# Input_Stage.net
KiCad netlist of a schematic drawn in Altium Designer
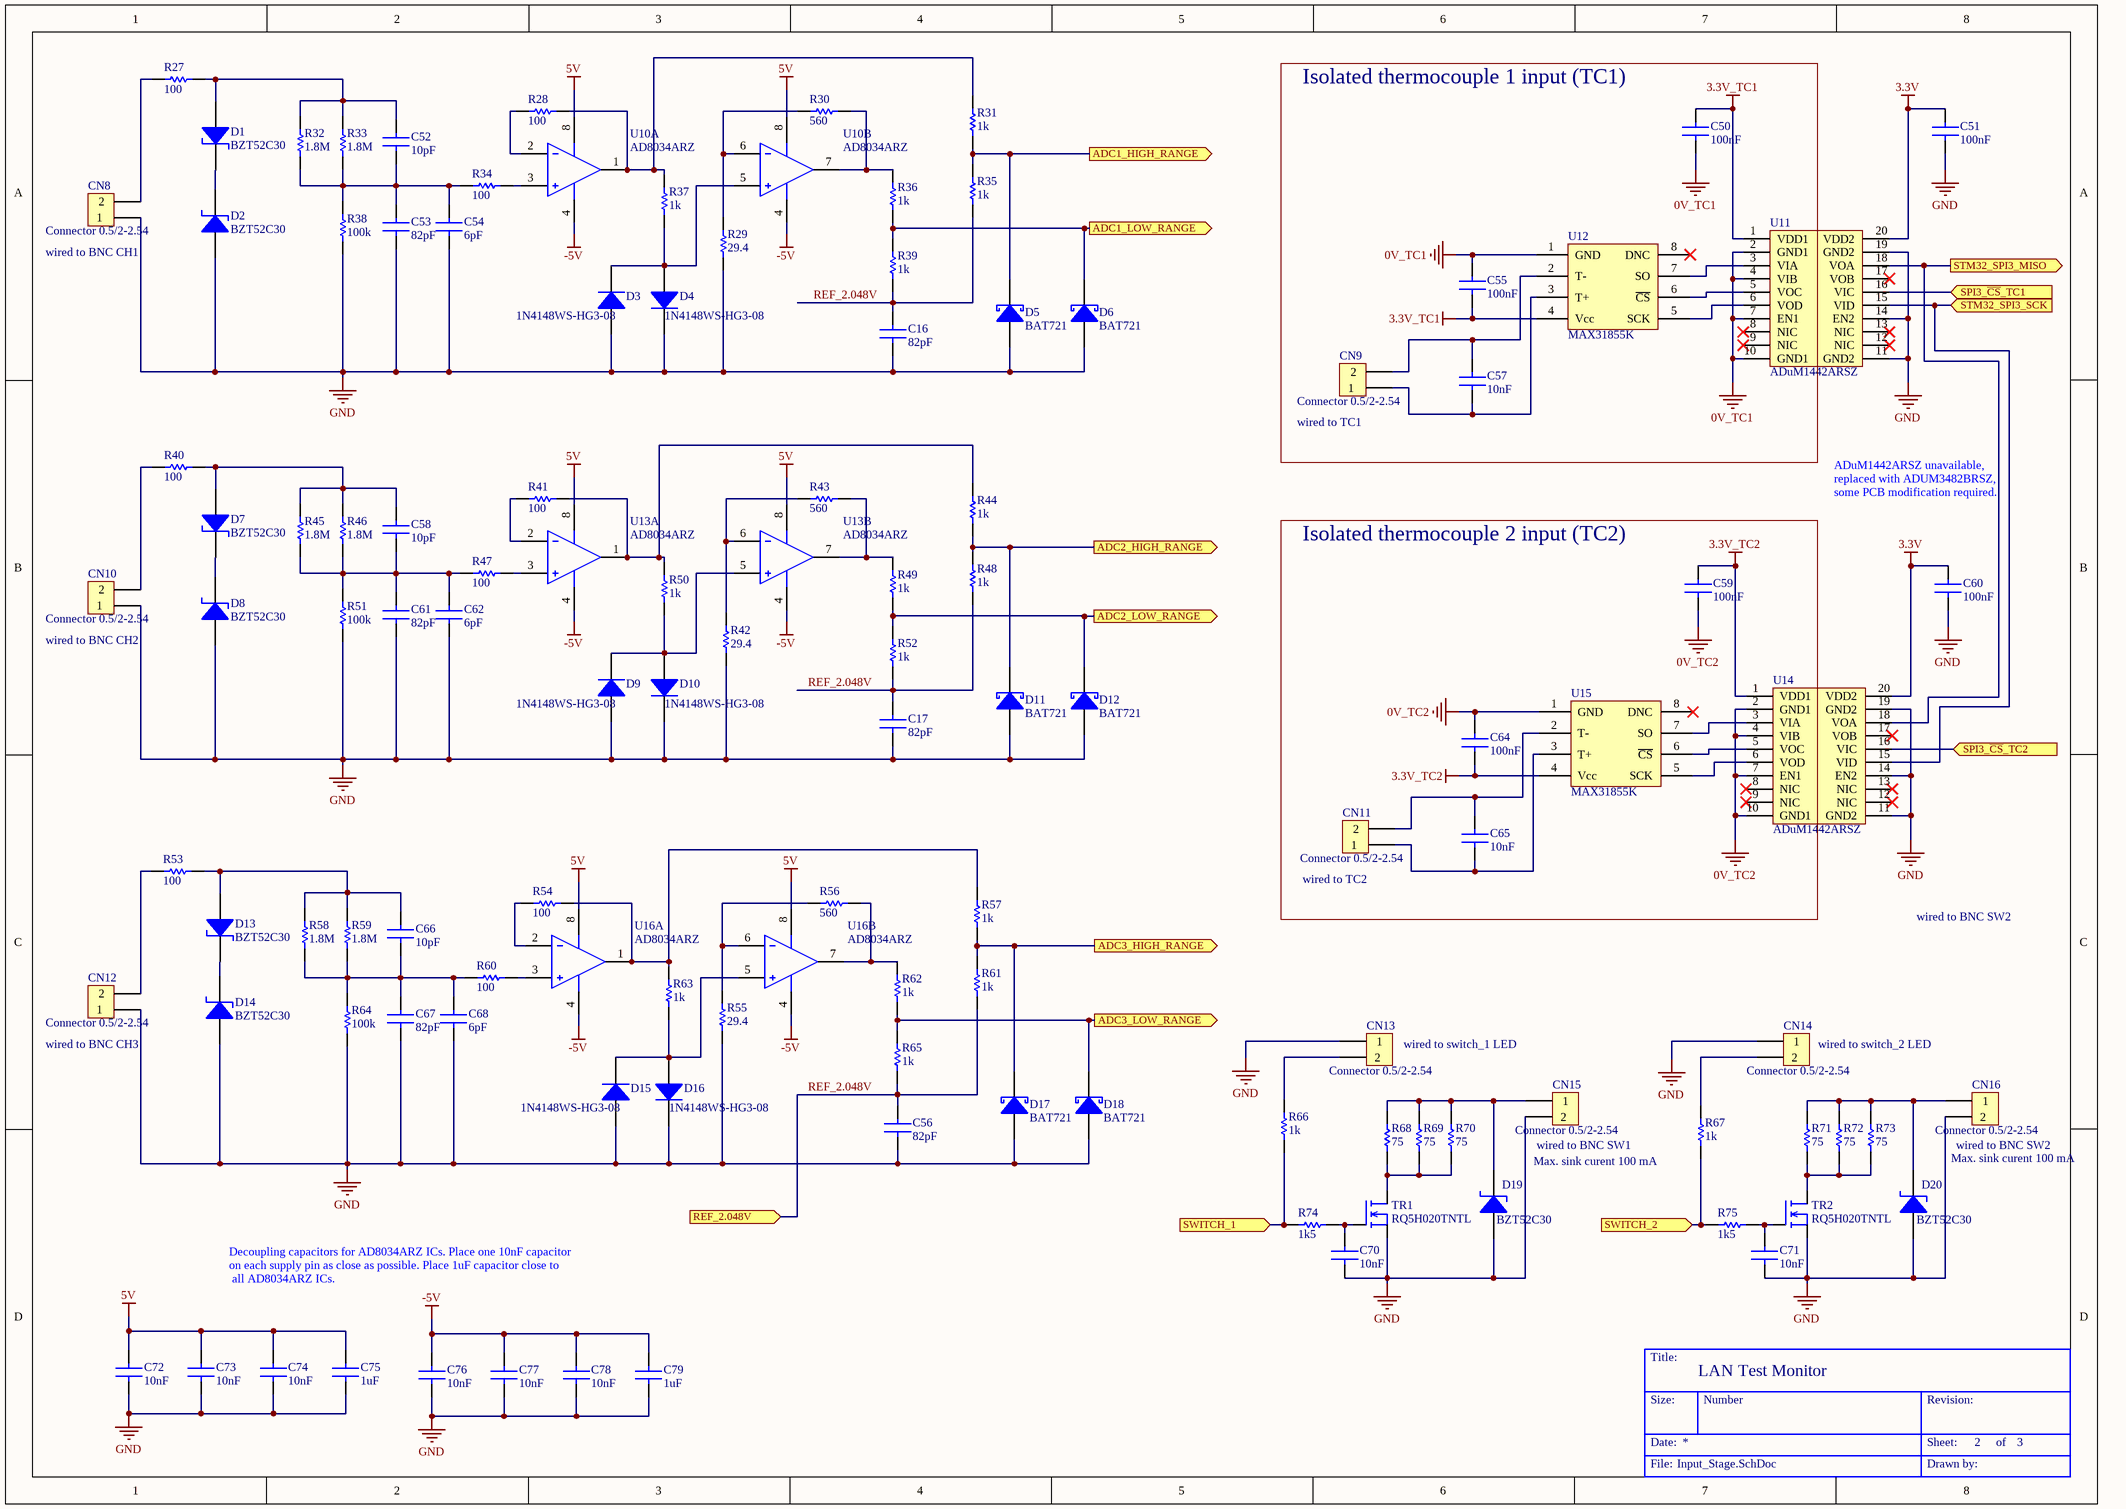
[diagram p0: Input_Stage.SchDoc]

(export (version "E")
  (design (tool "Eeschema 10.0.6"))
  (components
    (comp (ref "C16")
      (value "82pF")
      (footprint "Cap_0603")
      (libsource (lib "altium-import") (part "root_1_Cap 82pF 0603 10%_"))
    )
    (comp (ref "C17")
      (value "82pF")
      (footprint "Cap_0603")
      (libsource (lib "altium-import") (part "root_1_Cap 82pF 0603 10%_"))
    )
    (comp (ref "C50")
      (value "100nF")
      (footprint "Cap_0603")
      (libsource (lib "Schlib1") (part "Cap 100nF 0603 10%"))
    )
    (comp (ref "C51")
      (value "100nF")
      (footprint "Cap_0603")
      (libsource (lib "Schlib1") (part "Cap 100nF 0603 10%"))
    )
    (comp (ref "C52")
      (value "10pF")
      (footprint "Cap_0603")
      (libsource (lib "Schlib1") (part "Cap 10pF 0603 10%"))
    )
    (comp (ref "C53")
      (value "82pF")
      (footprint "Cap_0603")
      (libsource (lib "Schlib1") (part "Cap 82pF 0603 10%"))
    )
    (comp (ref "C54")
      (value "6pF")
      (footprint "Cap_0603")
      (libsource (lib "Schlib1") (part "Cap 6pF 0603 10%"))
    )
    (comp (ref "C55")
      (value "100nF")
      (footprint "Cap_0603")
      (libsource (lib "Schlib1") (part "Cap 100nF 0603 10%"))
    )
    (comp (ref "C56")
      (value "82pF")
      (footprint "Cap_0603")
      (libsource (lib "altium-import") (part "root_1_Cap 82pF 0603 10%_"))
    )
    (comp (ref "C57")
      (value "10nF")
      (footprint "Cap_0603")
      (libsource (lib "Schlib1") (part "Cap 10nF 0603 10%"))
    )
    (comp (ref "C58")
      (value "10pF")
      (footprint "Cap_0603")
      (libsource (lib "Schlib1") (part "Cap 10pF 0603 10%"))
    )
    (comp (ref "C59")
      (value "100nF")
      (footprint "Cap_0603")
      (libsource (lib "Schlib1") (part "Cap 100nF 0603 10%"))
    )
    (comp (ref "C60")
      (value "100nF")
      (footprint "Cap_0603")
      (libsource (lib "Schlib1") (part "Cap 100nF 0603 10%"))
    )
    (comp (ref "C61")
      (value "82pF")
      (footprint "Cap_0603")
      (libsource (lib "Schlib1") (part "Cap 82pF 0603 10%"))
    )
    (comp (ref "C62")
      (value "6pF")
      (footprint "Cap_0603")
      (libsource (lib "Schlib1") (part "Cap 6pF 0603 10%"))
    )
    (comp (ref "C64")
      (value "100nF")
      (footprint "Cap_0603")
      (libsource (lib "Schlib1") (part "Cap 100nF 0603 10%"))
    )
    (comp (ref "C65")
      (value "10nF")
      (footprint "Cap_0603")
      (libsource (lib "Schlib1") (part "Cap 10nF 0603 10%"))
    )
    (comp (ref "C66")
      (value "10pF")
      (footprint "Cap_0603")
      (libsource (lib "Schlib1") (part "Cap 10pF 0603 10%"))
    )
    (comp (ref "C67")
      (value "82pF")
      (footprint "Cap_0603")
      (libsource (lib "Schlib1") (part "Cap 82pF 0603 10%"))
    )
    (comp (ref "C68")
      (value "6pF")
      (footprint "Cap_0603")
      (libsource (lib "Schlib1") (part "Cap 6pF 0603 10%"))
    )
    (comp (ref "C70")
      (value "10nF")
      (footprint "Cap_0603")
      (libsource (lib "Schlib1") (part "Cap 10nF 0603 10%"))
    )
    (comp (ref "C71")
      (value "10nF")
      (footprint "Cap_0603")
      (libsource (lib "Schlib1") (part "Cap 10nF 0603 10%"))
    )
    (comp (ref "C72")
      (value "10nF")
      (footprint "Cap_0603")
      (libsource (lib "Schlib1") (part "Cap 10nF 0603 10%"))
    )
    (comp (ref "C73")
      (value "10nF")
      (footprint "Cap_0603")
      (libsource (lib "Schlib1") (part "Cap 10nF 0603 10%"))
    )
    (comp (ref "C74")
      (value "10nF")
      (footprint "Cap_0603")
      (libsource (lib "Schlib1") (part "Cap 10nF 0603 10%"))
    )
    (comp (ref "C75")
      (value "1uF")
      (footprint "Cap_0603")
      (libsource (lib "Schlib1") (part "Cap 1uF 0603 10%"))
    )
    (comp (ref "C76")
      (value "10nF")
      (footprint "Cap_0603")
      (libsource (lib "Schlib1") (part "Cap 10nF 0603 10%"))
    )
    (comp (ref "C77")
      (value "10nF")
      (footprint "Cap_0603")
      (libsource (lib "Schlib1") (part "Cap 10nF 0603 10%"))
    )
    (comp (ref "C78")
      (value "10nF")
      (footprint "Cap_0603")
      (libsource (lib "Schlib1") (part "Cap 10nF 0603 10%"))
    )
    (comp (ref "C79")
      (value "1uF")
      (footprint "Cap_0603")
      (libsource (lib "Schlib1") (part "Cap 1uF 0603 10%"))
    )
    (comp (ref "CN8")
      (value "Connector 0.5/2-2.54")
      (footprint "Connector 0.5/2-2.54")
      (description "Phoenix Contact MPT 0.5/2-2.54")
      (libsource (lib "") (part "Phoenix Contact MPT 0.5/2-2.54_1"))
    )
    (comp (ref "CN9")
      (value "Connector 0.5/2-2.54")
      (footprint "Connector 0.5/2-2.54")
      (description "Phoenix Contact MPT 0.5/2-2.54")
      (libsource (lib "") (part "Phoenix Contact MPT 0.5/2-2.54_1"))
    )
    (comp (ref "CN10")
      (value "Connector 0.5/2-2.54")
      (footprint "Connector 0.5/2-2.54")
      (description "Phoenix Contact MPT 0.5/2-2.54")
      (libsource (lib "") (part "Phoenix Contact MPT 0.5/2-2.54_1"))
    )
    (comp (ref "CN11")
      (value "Connector 0.5/2-2.54")
      (footprint "Connector 0.5/2-2.54")
      (description "Phoenix Contact MPT 0.5/2-2.54")
      (libsource (lib "") (part "Phoenix Contact MPT 0.5/2-2.54_1"))
    )
    (comp (ref "CN12")
      (value "Connector 0.5/2-2.54")
      (footprint "Connector 0.5/2-2.54")
      (description "Phoenix Contact MPT 0.5/2-2.54")
      (libsource (lib "") (part "Phoenix Contact MPT 0.5/2-2.54_1"))
    )
    (comp (ref "CN13")
      (value "Connector 0.5/2-2.54")
      (footprint "Connector 0.5/2-2.54")
      (description "Phoenix Contact MPT 0.5/2-2.54")
      (libsource (lib "Schlib1") (part "Phoenix Contact MPT 0.5/2-2.54"))
    )
    (comp (ref "CN14")
      (value "Connector 0.5/2-2.54")
      (footprint "Connector 0.5/2-2.54")
      (description "Phoenix Contact MPT 0.5/2-2.54")
      (libsource (lib "Schlib1") (part "Phoenix Contact MPT 0.5/2-2.54"))
    )
    (comp (ref "CN15")
      (value "Connector 0.5/2-2.54")
      (footprint "Connector 0.5/2-2.54")
      (description "Phoenix Contact MPT 0.5/2-2.54")
      (libsource (lib "Schlib1") (part "Phoenix Contact MPT 0.5/2-2.54"))
    )
    (comp (ref "CN16")
      (value "Connector 0.5/2-2.54")
      (footprint "Connector 0.5/2-2.54")
      (description "Phoenix Contact MPT 0.5/2-2.54")
      (libsource (lib "Schlib1") (part "Phoenix Contact MPT 0.5/2-2.54"))
    )
    (comp (ref "D1")
      (value "BZT52C30")
      (footprint "SOD123 BZT52C30")
      (description "Zener Diode")
      (fields (field (name "PUBLISHER") "Altium Limited"))
      (libsource (lib "Schlib1") (part "zener diode BZT52C30"))
    )
    (comp (ref "D2")
      (value "BZT52C30")
      (footprint "SOD123 BZT52C30")
      (description "Zener Diode")
      (fields (field (name "PUBLISHER") "Altium Limited"))
      (libsource (lib "Schlib1") (part "zener diode BZT52C30"))
    )
    (comp (ref "D3")
      (value "1N4148WS-HG3-08")
      (footprint "SOD-323 diode 1N4148WS-HG3-08")
      (fields (field (name "PUBLISHER") "Altium Limited"))
      (libsource (lib "Schlib1") (part "Diode 1N4148WS-HG3-08"))
    )
    (comp (ref "D4")
      (value "1N4148WS-HG3-08")
      (footprint "SOD-323 diode 1N4148WS-HG3-08")
      (fields (field (name "PUBLISHER") "Altium Limited"))
      (libsource (lib "Schlib1") (part "Diode 1N4148WS-HG3-08"))
    )
    (comp (ref "D5")
      (value "BAT721")
      (footprint "SOT23 BAT721")
      (description "Schottky diode BAT721")
      (fields (field (name "PUBLISHER") "Altium Limited"))
      (libsource (lib "Schlib1") (part "Diode BAT721"))
    )
    (comp (ref "D6")
      (value "BAT721")
      (footprint "SOT23 BAT721")
      (description "Schottky diode BAT721")
      (fields (field (name "PUBLISHER") "Altium Limited"))
      (libsource (lib "Schlib1") (part "Diode BAT721"))
    )
    (comp (ref "D7")
      (value "BZT52C30")
      (footprint "SOD123 BZT52C30")
      (description "Zener Diode")
      (fields (field (name "PUBLISHER") "Altium Limited"))
      (libsource (lib "Schlib1") (part "zener diode BZT52C30"))
    )
    (comp (ref "D8")
      (value "BZT52C30")
      (footprint "SOD123 BZT52C30")
      (description "Zener Diode")
      (fields (field (name "PUBLISHER") "Altium Limited"))
      (libsource (lib "Schlib1") (part "zener diode BZT52C30"))
    )
    (comp (ref "D9")
      (value "1N4148WS-HG3-08")
      (footprint "SOD-323 diode 1N4148WS-HG3-08")
      (fields (field (name "PUBLISHER") "Altium Limited"))
      (libsource (lib "Schlib1") (part "Diode 1N4148WS-HG3-08"))
    )
    (comp (ref "D10")
      (value "1N4148WS-HG3-08")
      (footprint "SOD-323 diode 1N4148WS-HG3-08")
      (fields (field (name "PUBLISHER") "Altium Limited"))
      (libsource (lib "Schlib1") (part "Diode 1N4148WS-HG3-08"))
    )
    (comp (ref "D11")
      (value "BAT721")
      (footprint "SOT23 BAT721")
      (description "Schottky diode BAT721")
      (fields (field (name "PUBLISHER") "Altium Limited"))
      (libsource (lib "Schlib1") (part "Diode BAT721"))
    )
    (comp (ref "D12")
      (value "BAT721")
      (footprint "SOT23 BAT721")
      (description "Schottky diode BAT721")
      (fields (field (name "PUBLISHER") "Altium Limited"))
      (libsource (lib "Schlib1") (part "Diode BAT721"))
    )
    (comp (ref "D13")
      (value "BZT52C30")
      (footprint "SOD123 BZT52C30")
      (description "Zener Diode")
      (fields (field (name "PUBLISHER") "Altium Limited"))
      (libsource (lib "Schlib1") (part "zener diode BZT52C30"))
    )
    (comp (ref "D14")
      (value "BZT52C30")
      (footprint "SOD123 BZT52C30")
      (description "Zener Diode")
      (fields (field (name "PUBLISHER") "Altium Limited"))
      (libsource (lib "Schlib1") (part "zener diode BZT52C30"))
    )
    (comp (ref "D15")
      (value "1N4148WS-HG3-08")
      (footprint "SOD-323 diode 1N4148WS-HG3-08")
      (fields (field (name "PUBLISHER") "Altium Limited"))
      (libsource (lib "Schlib1") (part "Diode 1N4148WS-HG3-08"))
    )
    (comp (ref "D16")
      (value "1N4148WS-HG3-08")
      (footprint "SOD-323 diode 1N4148WS-HG3-08")
      (fields (field (name "PUBLISHER") "Altium Limited"))
      (libsource (lib "Schlib1") (part "Diode 1N4148WS-HG3-08"))
    )
    (comp (ref "D17")
      (value "BAT721")
      (footprint "SOT23 BAT721")
      (description "Schottky diode BAT721")
      (fields (field (name "PUBLISHER") "Altium Limited"))
      (libsource (lib "Schlib1") (part "Diode BAT721"))
    )
    (comp (ref "D18")
      (value "BAT721")
      (footprint "SOT23 BAT721")
      (description "Schottky diode BAT721")
      (fields (field (name "PUBLISHER") "Altium Limited"))
      (libsource (lib "Schlib1") (part "Diode BAT721"))
    )
    (comp (ref "D19")
      (value "BZT52C30")
      (footprint "SOD123 BZT52C30")
      (description "Zener Diode")
      (fields (field (name "PUBLISHER") "Altium Limited"))
      (libsource (lib "Schlib1") (part "zener diode BZT52C30"))
    )
    (comp (ref "D20")
      (value "BZT52C30")
      (footprint "SOD123 BZT52C30")
      (description "Zener Diode")
      (fields (field (name "PUBLISHER") "Altium Limited"))
      (libsource (lib "Schlib1") (part "zener diode BZT52C30"))
    )
    (comp (ref "R27")
      (value "100")
      (footprint "Res_0603")
      (libsource (lib "Schlib1") (part "Res 100 1% 0603"))
    )
    (comp (ref "R28")
      (value "100")
      (footprint "Res_0603")
      (libsource (lib "Schlib1") (part "Res 100 1% 0603"))
    )
    (comp (ref "R29")
      (value "29.4")
      (footprint "Res_0603")
      (libsource (lib "Schlib1") (part "Res 29.4 1% 0603"))
    )
    (comp (ref "R30")
      (value "560")
      (footprint "Res_0603")
      (libsource (lib "Schlib1") (part "Res 560 1% 0603"))
    )
    (comp (ref "R31")
      (value "1k")
      (footprint "PcbLib1:Res_0603")
      (libsource (lib "Schlib1") (part "Res 1k 1% 0603"))
    )
    (comp (ref "R32")
      (value "1.8M")
      (footprint "Res_0603")
      (libsource (lib "Schlib1") (part "Res 1.8M 1% 0603"))
    )
    (comp (ref "R33")
      (value "1.8M")
      (footprint "Res_0603")
      (libsource (lib "Schlib1") (part "Res 1.8M 1% 0603"))
    )
    (comp (ref "R34")
      (value "100")
      (footprint "Res_0603")
      (libsource (lib "Schlib1") (part "Res 100 1% 0603"))
    )
    (comp (ref "R35")
      (value "1k")
      (footprint "PcbLib1:Res_0603")
      (libsource (lib "Schlib1") (part "Res 1k 1% 0603"))
    )
    (comp (ref "R36")
      (value "1k")
      (footprint "PcbLib1:Res_0603")
      (libsource (lib "Schlib1") (part "Res 1k 1% 0603"))
    )
    (comp (ref "R37")
      (value "1k")
      (footprint "PcbLib1:Res_0603")
      (libsource (lib "Schlib1") (part "Res 1k 1% 0603"))
    )
    (comp (ref "R38")
      (value "100k")
      (footprint "Res_0603")
      (libsource (lib "Schlib1") (part "Res 100k 1% 0603"))
    )
    (comp (ref "R39")
      (value "1k")
      (footprint "PcbLib1:Res_0603")
      (libsource (lib "Schlib1") (part "Res 1k 1% 0603"))
    )
    (comp (ref "R40")
      (value "100")
      (footprint "Res_0603")
      (libsource (lib "Schlib1") (part "Res 100 1% 0603"))
    )
    (comp (ref "R41")
      (value "100")
      (footprint "Res_0603")
      (libsource (lib "Schlib1") (part "Res 100 1% 0603"))
    )
    (comp (ref "R42")
      (value "29.4")
      (footprint "Res_0603")
      (libsource (lib "Schlib1") (part "Res 29.4 1% 0603"))
    )
    (comp (ref "R43")
      (value "560")
      (footprint "Res_0603")
      (libsource (lib "Schlib1") (part "Res 560 1% 0603"))
    )
    (comp (ref "R44")
      (value "1k")
      (footprint "PcbLib1:Res_0603")
      (libsource (lib "Schlib1") (part "Res 1k 1% 0603"))
    )
    (comp (ref "R45")
      (value "1.8M")
      (footprint "Res_0603")
      (libsource (lib "Schlib1") (part "Res 1.8M 1% 0603"))
    )
    (comp (ref "R46")
      (value "1.8M")
      (footprint "Res_0603")
      (libsource (lib "Schlib1") (part "Res 1.8M 1% 0603"))
    )
    (comp (ref "R47")
      (value "100")
      (footprint "Res_0603")
      (libsource (lib "Schlib1") (part "Res 100 1% 0603"))
    )
    (comp (ref "R48")
      (value "1k")
      (footprint "PcbLib1:Res_0603")
      (libsource (lib "Schlib1") (part "Res 1k 1% 0603"))
    )
    (comp (ref "R49")
      (value "1k")
      (footprint "PcbLib1:Res_0603")
      (libsource (lib "Schlib1") (part "Res 1k 1% 0603"))
    )
    (comp (ref "R50")
      (value "1k")
      (footprint "PcbLib1:Res_0603")
      (libsource (lib "Schlib1") (part "Res 1k 1% 0603"))
    )
    (comp (ref "R51")
      (value "100k")
      (footprint "Res_0603")
      (libsource (lib "Schlib1") (part "Res 100k 1% 0603"))
    )
    (comp (ref "R52")
      (value "1k")
      (footprint "PcbLib1:Res_0603")
      (libsource (lib "Schlib1") (part "Res 1k 1% 0603"))
    )
    (comp (ref "R53")
      (value "100")
      (footprint "Res_0603")
      (libsource (lib "Schlib1") (part "Res 100 1% 0603"))
    )
    (comp (ref "R54")
      (value "100")
      (footprint "Res_0603")
      (libsource (lib "Schlib1") (part "Res 100 1% 0603"))
    )
    (comp (ref "R55")
      (value "29.4")
      (footprint "Res_0603")
      (libsource (lib "Schlib1") (part "Res 29.4 1% 0603"))
    )
    (comp (ref "R56")
      (value "560")
      (footprint "Res_0603")
      (libsource (lib "Schlib1") (part "Res 560 1% 0603"))
    )
    (comp (ref "R57")
      (value "1k")
      (footprint "PcbLib1:Res_0603")
      (libsource (lib "Schlib1") (part "Res 1k 1% 0603"))
    )
    (comp (ref "R58")
      (value "1.8M")
      (footprint "Res_0603")
      (libsource (lib "Schlib1") (part "Res 1.8M 1% 0603"))
    )
    (comp (ref "R59")
      (value "1.8M")
      (footprint "Res_0603")
      (libsource (lib "Schlib1") (part "Res 1.8M 1% 0603"))
    )
    (comp (ref "R60")
      (value "100")
      (footprint "Res_0603")
      (libsource (lib "Schlib1") (part "Res 100 1% 0603"))
    )
    (comp (ref "R61")
      (value "1k")
      (footprint "PcbLib1:Res_0603")
      (libsource (lib "Schlib1") (part "Res 1k 1% 0603"))
    )
    (comp (ref "R62")
      (value "1k")
      (footprint "PcbLib1:Res_0603")
      (libsource (lib "Schlib1") (part "Res 1k 1% 0603"))
    )
    (comp (ref "R63")
      (value "1k")
      (footprint "PcbLib1:Res_0603")
      (libsource (lib "Schlib1") (part "Res 1k 1% 0603"))
    )
    (comp (ref "R64")
      (value "100k")
      (footprint "Res_0603")
      (libsource (lib "Schlib1") (part "Res 100k 1% 0603"))
    )
    (comp (ref "R65")
      (value "1k")
      (footprint "PcbLib1:Res_0603")
      (libsource (lib "Schlib1") (part "Res 1k 1% 0603"))
    )
    (comp (ref "R66")
      (value "1k")
      (footprint "PcbLib1:Res_0603")
      (libsource (lib "Schlib1") (part "Res 1k 1% 0603"))
    )
    (comp (ref "R67")
      (value "1k")
      (footprint "PcbLib1:Res_0603")
      (libsource (lib "Schlib1") (part "Res 1k 1% 0603"))
    )
    (comp (ref "R68") (value "75") (footprint "Res_0603") (libsource (lib "Schlib1") (part "Res 75 1% 0603")))
    (comp (ref "R69") (value "75") (footprint "Res_0603") (libsource (lib "Schlib1") (part "Res 75 1% 0603")))
    (comp (ref "R70") (value "75") (footprint "Res_0603") (libsource (lib "Schlib1") (part "Res 75 1% 0603")))
    (comp (ref "R71") (value "75") (footprint "Res_0603") (libsource (lib "Schlib1") (part "Res 75 1% 0603")))
    (comp (ref "R72") (value "75") (footprint "Res_0603") (libsource (lib "Schlib1") (part "Res 75 1% 0603")))
    (comp (ref "R73") (value "75") (footprint "Res_0603") (libsource (lib "Schlib1") (part "Res 75 1% 0603")))
    (comp (ref "R74")
      (value "1k5")
      (footprint "Res_0603")
      (libsource (lib "Schlib1") (part "Res 1k5 1% 0603"))
    )
    (comp (ref "R75")
      (value "1k5")
      (footprint "Res_0603")
      (libsource (lib "Schlib1") (part "Res 1k5 1% 0603"))
    )
    (comp (ref "TR1")
      (value "RQ5H020TNTL")
      (footprint "SOT-346-3 RQ5H020TN")
      (description "MOSFET N-CH 60V 2A 500mW")
      (libsource (lib "Schlib1") (part "RQ5H020TNTL"))
    )
    (comp (ref "TR2")
      (value "RQ5H020TNTL")
      (footprint "SOT-346-3 RQ5H020TN")
      (description "MOSFET N-CH 60V 2A 500mW")
      (libsource (lib "Schlib1") (part "RQ5H020TNTL"))
    )
    (comp (ref "U10")
      (value "AD8034ARZ")
      (footprint "8-SOIC_N AD8034ARZ")
      (description "dual op amp")
      (fields (field (name "PUBLISHER") "Altium Limited"))
      (libsource (lib "Schlib1") (part "AD8034ARZ"))
    )
    (comp (ref "U11")
      (value "ADuM1442ARSZ")
      (footprint "SSOP ADuM1442ARSZ")
      (description "ADuM1442ARSZ isolator")
      (libsource (lib "Schlib1") (part "ADuM1442ARSZ"))
    )
    (comp (ref "U12")
      (value "MAX31855K")
      (footprint "SOIC127P600X175-8N")
      (description "Thermocouple to digital converter")
      (libsource (lib "Schlib1") (part "MAX31855K"))
    )
    (comp (ref "U13")
      (value "AD8034ARZ")
      (footprint "8-SOIC_N AD8034ARZ")
      (description "dual op amp")
      (fields (field (name "PUBLISHER") "Altium Limited"))
      (libsource (lib "Schlib1") (part "AD8034ARZ"))
    )
    (comp (ref "U14")
      (value "ADuM1442ARSZ")
      (footprint "SSOP ADuM1442ARSZ")
      (description "ADuM1442ARSZ isolator")
      (libsource (lib "Schlib1") (part "ADuM1442ARSZ"))
    )
    (comp (ref "U15")
      (value "MAX31855K")
      (footprint "SOIC127P600X175-8N")
      (description "Thermocouple to digital converter")
      (libsource (lib "Schlib1") (part "MAX31855K"))
    )
    (comp (ref "U16")
      (value "AD8034ARZ")
      (footprint "8-SOIC_N AD8034ARZ")
      (description "dual op amp")
      (fields (field (name "PUBLISHER") "Altium Limited"))
      (libsource (lib "Schlib1") (part "AD8034ARZ"))
    )
  )
  (nets
    (net (code "1") (name "-5V") (class "Default")
      (node (ref "C76") (pin "2") (pinfunction "2_2") (pintype "passive"))
      (node (ref "C77") (pin "2") (pinfunction "2_2") (pintype "passive"))
      (node (ref "C78") (pin "2") (pinfunction "2_2") (pintype "passive"))
      (node (ref "C79") (pin "2") (pinfunction "2_2") (pintype "passive"))
      (node (ref "U10") (pin "4") (pinfunction "V-_4") (pintype "power_in"))
      (node (ref "U13") (pin "4") (pinfunction "V-_4") (pintype "power_in"))
      (node (ref "U16") (pin "4") (pinfunction "V-_4") (pintype "power_in"))
    )
    (net (code "2") (name "/ADC1_HIGH_RANGE") (class "Default")
      (node (ref "D5") (pin "2") (pinfunction "K_2") (pintype "passive"))
      (node (ref "R31") (pin "2") (pinfunction "2_2") (pintype "passive"))
      (node (ref "R35") (pin "1") (pinfunction "1_1") (pintype "passive"))
    )
    (net (code "3") (name "/ADC1_LOW_RANGE") (class "Default")
      (node (ref "D6") (pin "2") (pinfunction "K_2") (pintype "passive"))
      (node (ref "R36") (pin "2") (pinfunction "2_2") (pintype "passive"))
      (node (ref "R39") (pin "1") (pinfunction "1_1") (pintype "passive"))
    )
    (net (code "4") (name "/ADC2_HIGH_RANGE") (class "Default")
      (node (ref "D11") (pin "2") (pinfunction "K_2") (pintype "passive"))
      (node (ref "R44") (pin "2") (pinfunction "2_2") (pintype "passive"))
      (node (ref "R48") (pin "1") (pinfunction "1_1") (pintype "passive"))
    )
    (net (code "5") (name "/ADC2_LOW_RANGE") (class "Default")
      (node (ref "D12") (pin "2") (pinfunction "K_2") (pintype "passive"))
      (node (ref "R49") (pin "2") (pinfunction "2_2") (pintype "passive"))
      (node (ref "R52") (pin "1") (pinfunction "1_1") (pintype "passive"))
    )
    (net (code "6") (name "/ADC3_HIGH_RANGE") (class "Default")
      (node (ref "D17") (pin "2") (pinfunction "K_2") (pintype "passive"))
      (node (ref "R57") (pin "2") (pinfunction "2_2") (pintype "passive"))
      (node (ref "R61") (pin "1") (pinfunction "1_1") (pintype "passive"))
    )
    (net (code "7") (name "/ADC3_LOW_RANGE") (class "Default")
      (node (ref "D18") (pin "2") (pinfunction "K_2") (pintype "passive"))
      (node (ref "R62") (pin "2") (pinfunction "2_2") (pintype "passive"))
      (node (ref "R65") (pin "1") (pinfunction "1_1") (pintype "passive"))
    )
    (net (code "8") (name "/REF_2.048V") (class "Default")
      (node (ref "C16") (pin "2") (pinfunction "2_2") (pintype "passive"))
      (node (ref "C17") (pin "2") (pinfunction "2_2") (pintype "passive"))
      (node (ref "C56") (pin "2") (pinfunction "2_2") (pintype "passive"))
      (node (ref "R35") (pin "2") (pinfunction "2_2") (pintype "passive"))
      (node (ref "R39") (pin "2") (pinfunction "2_2") (pintype "passive"))
      (node (ref "R48") (pin "2") (pinfunction "2_2") (pintype "passive"))
      (node (ref "R52") (pin "2") (pinfunction "2_2") (pintype "passive"))
      (node (ref "R61") (pin "2") (pinfunction "2_2") (pintype "passive"))
      (node (ref "R65") (pin "2") (pinfunction "2_2") (pintype "passive"))
    )
    (net (code "9") (name "/SPI3_~{CS}_TC1") (class "Default")
      (node (ref "U11") (pin "16") (pinfunction "VIC_16") (pintype "passive"))
    )
    (net (code "10") (name "/SPI3_~{CS}_TC2") (class "Default")
      (node (ref "U14") (pin "16") (pinfunction "VIC_16") (pintype "passive"))
    )
    (net (code "11") (name "/STM32_SPI3_MISO") (class "Default")
      (node (ref "U11") (pin "18") (pinfunction "VOA_18") (pintype "passive"))
      (node (ref "U14") (pin "18") (pinfunction "VOA_18") (pintype "passive"))
    )
    (net (code "12") (name "/STM32_SPI3_SCK") (class "Default")
      (node (ref "U11") (pin "15") (pinfunction "VID_15") (pintype "passive"))
      (node (ref "U14") (pin "15") (pinfunction "VID_15") (pintype "passive"))
    )
    (net (code "13") (name "/SWITCH_1") (class "Default")
      (node (ref "R66") (pin "1") (pinfunction "1_1") (pintype "passive"))
      (node (ref "R74") (pin "1") (pinfunction "1_1") (pintype "passive"))
    )
    (net (code "14") (name "/SWITCH_2") (class "Default")
      (node (ref "R67") (pin "1") (pinfunction "1_1") (pintype "passive"))
      (node (ref "R75") (pin "1") (pinfunction "1_1") (pintype "passive"))
    )
    (net (code "15") (name "0V_TC1") (class "Default")
      (node (ref "C50") (pin "1") (pinfunction "1_1") (pintype "passive"))
      (node (ref "C55") (pin "2") (pinfunction "2_2") (pintype "passive"))
      (node (ref "U11") (pin "10") (pinfunction "GND1_10") (pintype "passive"))
      (node (ref "U11") (pin "2") (pinfunction "GND1_2") (pintype "passive"))
      (node (ref "U11") (pin "4") (pinfunction "VIB_4") (pintype "passive"))
      (node (ref "U11") (pin "7") (pinfunction "EN1_7") (pintype "passive"))
      (node (ref "U12") (pin "1") (pinfunction "GND_1") (pintype "passive"))
    )
    (net (code "16") (name "0V_TC2") (class "Default")
      (node (ref "C59") (pin "1") (pinfunction "1_1") (pintype "passive"))
      (node (ref "C64") (pin "2") (pinfunction "2_2") (pintype "passive"))
      (node (ref "U14") (pin "10") (pinfunction "GND1_10") (pintype "passive"))
      (node (ref "U14") (pin "2") (pinfunction "GND1_2") (pintype "passive"))
      (node (ref "U14") (pin "4") (pinfunction "VIB_4") (pintype "passive"))
      (node (ref "U14") (pin "7") (pinfunction "EN1_7") (pintype "passive"))
      (node (ref "U15") (pin "1") (pinfunction "GND_1") (pintype "passive"))
    )
    (net (code "17") (name "3.3V") (class "Default")
      (node (ref "C51") (pin "2") (pinfunction "2_2") (pintype "passive"))
      (node (ref "C60") (pin "2") (pinfunction "2_2") (pintype "passive"))
      (node (ref "U11") (pin "20") (pinfunction "VDD2_20") (pintype "passive"))
      (node (ref "U14") (pin "20") (pinfunction "VDD2_20") (pintype "passive"))
    )
    (net (code "18") (name "3.3V_TC1") (class "Default")
      (node (ref "C50") (pin "2") (pinfunction "2_2") (pintype "passive"))
      (node (ref "C55") (pin "1") (pinfunction "1_1") (pintype "passive"))
      (node (ref "U11") (pin "1") (pinfunction "VDD1_1") (pintype "passive"))
      (node (ref "U12") (pin "4") (pinfunction "Vcc_4") (pintype "passive"))
    )
    (net (code "19") (name "3.3V_TC2") (class "Default")
      (node (ref "C59") (pin "2") (pinfunction "2_2") (pintype "passive"))
      (node (ref "C64") (pin "1") (pinfunction "1_1") (pintype "passive"))
      (node (ref "U14") (pin "1") (pinfunction "VDD1_1") (pintype "passive"))
      (node (ref "U15") (pin "4") (pinfunction "Vcc_4") (pintype "passive"))
    )
    (net (code "20") (name "5V") (class "Default")
      (node (ref "C72") (pin "2") (pinfunction "2_2") (pintype "passive"))
      (node (ref "C73") (pin "2") (pinfunction "2_2") (pintype "passive"))
      (node (ref "C74") (pin "2") (pinfunction "2_2") (pintype "passive"))
      (node (ref "C75") (pin "2") (pinfunction "2_2") (pintype "passive"))
      (node (ref "U10") (pin "8") (pinfunction "V+_8") (pintype "power_in"))
      (node (ref "U13") (pin "8") (pinfunction "V+_8") (pintype "power_in"))
      (node (ref "U16") (pin "8") (pinfunction "V+_8") (pintype "power_in"))
    )
    (net (code "21") (name "GND") (class "Default")
      (node (ref "C16") (pin "1") (pinfunction "1_1") (pintype "passive"))
      (node (ref "C17") (pin "1") (pinfunction "1_1") (pintype "passive"))
      (node (ref "C51") (pin "1") (pinfunction "1_1") (pintype "passive"))
      (node (ref "C53") (pin "1") (pinfunction "1_1") (pintype "passive"))
      (node (ref "C54") (pin "1") (pinfunction "1_1") (pintype "passive"))
      (node (ref "C56") (pin "1") (pinfunction "1_1") (pintype "passive"))
      (node (ref "C60") (pin "1") (pinfunction "1_1") (pintype "passive"))
      (node (ref "C61") (pin "1") (pinfunction "1_1") (pintype "passive"))
      (node (ref "C62") (pin "1") (pinfunction "1_1") (pintype "passive"))
      (node (ref "C67") (pin "1") (pinfunction "1_1") (pintype "passive"))
      (node (ref "C68") (pin "1") (pinfunction "1_1") (pintype "passive"))
      (node (ref "C70") (pin "2") (pinfunction "2_2") (pintype "passive"))
      (node (ref "C71") (pin "2") (pinfunction "2_2") (pintype "passive"))
      (node (ref "C72") (pin "1") (pinfunction "1_1") (pintype "passive"))
      (node (ref "C73") (pin "1") (pinfunction "1_1") (pintype "passive"))
      (node (ref "C74") (pin "1") (pinfunction "1_1") (pintype "passive"))
      (node (ref "C75") (pin "1") (pinfunction "1_1") (pintype "passive"))
      (node (ref "C76") (pin "1") (pinfunction "1_1") (pintype "passive"))
      (node (ref "C77") (pin "1") (pinfunction "1_1") (pintype "passive"))
      (node (ref "C78") (pin "1") (pinfunction "1_1") (pintype "passive"))
      (node (ref "C79") (pin "1") (pinfunction "1_1") (pintype "passive"))
      (node (ref "CN10") (pin "1") (pinfunction "1_1") (pintype "passive"))
      (node (ref "CN12") (pin "1") (pinfunction "1_1") (pintype "passive"))
      (node (ref "CN13") (pin "1") (pinfunction "1_1") (pintype "passive"))
      (node (ref "CN14") (pin "1") (pinfunction "1_1") (pintype "passive"))
      (node (ref "CN15") (pin "2") (pinfunction "2_2") (pintype "passive"))
      (node (ref "CN16") (pin "2") (pinfunction "2_2") (pintype "passive"))
      (node (ref "CN8") (pin "1") (pinfunction "1_1") (pintype "passive"))
      (node (ref "D10") (pin "2") (pinfunction "K_2") (pintype "passive"))
      (node (ref "D11") (pin "1") (pinfunction "A_1") (pintype "passive"))
      (node (ref "D12") (pin "1") (pinfunction "A_1") (pintype "passive"))
      (node (ref "D14") (pin "1") (pinfunction "A_1") (pintype "passive"))
      (node (ref "D15") (pin "1") (pinfunction "A_1") (pintype "passive"))
      (node (ref "D16") (pin "2") (pinfunction "K_2") (pintype "passive"))
      (node (ref "D17") (pin "1") (pinfunction "A_1") (pintype "passive"))
      (node (ref "D18") (pin "1") (pinfunction "A_1") (pintype "passive"))
      (node (ref "D19") (pin "1") (pinfunction "A_1") (pintype "passive"))
      (node (ref "D2") (pin "1") (pinfunction "A_1") (pintype "passive"))
      (node (ref "D20") (pin "1") (pinfunction "A_1") (pintype "passive"))
      (node (ref "D3") (pin "1") (pinfunction "A_1") (pintype "passive"))
      (node (ref "D4") (pin "2") (pinfunction "K_2") (pintype "passive"))
      (node (ref "D5") (pin "1") (pinfunction "A_1") (pintype "passive"))
      (node (ref "D6") (pin "1") (pinfunction "A_1") (pintype "passive"))
      (node (ref "D8") (pin "1") (pinfunction "A_1") (pintype "passive"))
      (node (ref "D9") (pin "1") (pinfunction "A_1") (pintype "passive"))
      (node (ref "R29") (pin "1") (pinfunction "1_1") (pintype "passive"))
      (node (ref "R38") (pin "1") (pinfunction "1_1") (pintype "passive"))
      (node (ref "R42") (pin "1") (pinfunction "1_1") (pintype "passive"))
      (node (ref "R51") (pin "1") (pinfunction "1_1") (pintype "passive"))
      (node (ref "R55") (pin "1") (pinfunction "1_1") (pintype "passive"))
      (node (ref "R64") (pin "1") (pinfunction "1_1") (pintype "passive"))
      (node (ref "TR1") (pin "3") (pinfunction "3_3") (pintype "passive"))
      (node (ref "TR2") (pin "3") (pinfunction "3_3") (pintype "passive"))
      (node (ref "U11") (pin "11") (pinfunction "GND2_11") (pintype "passive"))
      (node (ref "U11") (pin "14") (pinfunction "EN2_14") (pintype "passive"))
      (node (ref "U11") (pin "19") (pinfunction "GND2_19") (pintype "passive"))
      (node (ref "U14") (pin "11") (pinfunction "GND2_11") (pintype "passive"))
      (node (ref "U14") (pin "14") (pinfunction "EN2_14") (pintype "passive"))
      (node (ref "U14") (pin "19") (pinfunction "GND2_19") (pintype "passive"))
    )
    (net (code "22") (name "Net-(C52-Pad1)") (class "Default")
      (node (ref "C52") (pin "1") (pinfunction "1_1") (pintype "passive"))
      (node (ref "C53") (pin "2") (pinfunction "2_2") (pintype "passive"))
      (node (ref "C54") (pin "2") (pinfunction "2_2") (pintype "passive"))
      (node (ref "R32") (pin "1") (pinfunction "1_1") (pintype "passive"))
      (node (ref "R33") (pin "1") (pinfunction "1_1") (pintype "passive"))
      (node (ref "R34") (pin "1") (pinfunction "1_1") (pintype "passive"))
      (node (ref "R38") (pin "2") (pinfunction "2_2") (pintype "passive"))
    )
    (net (code "23") (name "Net-(C58-Pad1)") (class "Default")
      (node (ref "C58") (pin "1") (pinfunction "1_1") (pintype "passive"))
      (node (ref "C61") (pin "2") (pinfunction "2_2") (pintype "passive"))
      (node (ref "C62") (pin "2") (pinfunction "2_2") (pintype "passive"))
      (node (ref "R45") (pin "1") (pinfunction "1_1") (pintype "passive"))
      (node (ref "R46") (pin "1") (pinfunction "1_1") (pintype "passive"))
      (node (ref "R47") (pin "1") (pinfunction "1_1") (pintype "passive"))
      (node (ref "R51") (pin "2") (pinfunction "2_2") (pintype "passive"))
    )
    (net (code "24") (name "Net-(C66-Pad1)") (class "Default")
      (node (ref "C66") (pin "1") (pinfunction "1_1") (pintype "passive"))
      (node (ref "C67") (pin "2") (pinfunction "2_2") (pintype "passive"))
      (node (ref "C68") (pin "2") (pinfunction "2_2") (pintype "passive"))
      (node (ref "R58") (pin "1") (pinfunction "1_1") (pintype "passive"))
      (node (ref "R59") (pin "1") (pinfunction "1_1") (pintype "passive"))
      (node (ref "R60") (pin "1") (pinfunction "1_1") (pintype "passive"))
      (node (ref "R64") (pin "2") (pinfunction "2_2") (pintype "passive"))
    )
    (net (code "25") (name "Net-(C70-Pad1)") (class "Default")
      (node (ref "C70") (pin "1") (pinfunction "1_1") (pintype "passive"))
      (node (ref "R74") (pin "2") (pinfunction "2_2") (pintype "passive"))
      (node (ref "TR1") (pin "1") (pinfunction "1_1") (pintype "passive"))
    )
    (net (code "26") (name "Net-(C71-Pad1)") (class "Default")
      (node (ref "C71") (pin "1") (pinfunction "1_1") (pintype "passive"))
      (node (ref "R75") (pin "2") (pinfunction "2_2") (pintype "passive"))
      (node (ref "TR2") (pin "1") (pinfunction "1_1") (pintype "passive"))
    )
    (net (code "27") (name "Net-(CN8-Pad2)") (class "Default")
      (node (ref "CN8") (pin "2") (pinfunction "2_2") (pintype "passive"))
      (node (ref "R27") (pin "1") (pinfunction "1_1") (pintype "passive"))
    )
    (net (code "28") (name "Net-(CN10-Pad2)") (class "Default")
      (node (ref "CN10") (pin "2") (pinfunction "2_2") (pintype "passive"))
      (node (ref "R40") (pin "1") (pinfunction "1_1") (pintype "passive"))
    )
    (net (code "29") (name "Net-(CN12-Pad2)") (class "Default")
      (node (ref "CN12") (pin "2") (pinfunction "2_2") (pintype "passive"))
      (node (ref "R53") (pin "1") (pinfunction "1_1") (pintype "passive"))
    )
    (net (code "30") (name "Net-(CN13-Pad2)") (class "Default")
      (node (ref "CN13") (pin "2") (pinfunction "2_2") (pintype "passive"))
      (node (ref "R66") (pin "2") (pinfunction "2_2") (pintype "passive"))
    )
    (net (code "31") (name "Net-(CN14-Pad2)") (class "Default")
      (node (ref "CN14") (pin "2") (pinfunction "2_2") (pintype "passive"))
      (node (ref "R67") (pin "2") (pinfunction "2_2") (pintype "passive"))
    )
    (net (code "32") (name "Net-(D1-A)") (class "Default")
      (node (ref "C52") (pin "2") (pinfunction "2_2") (pintype "passive"))
      (node (ref "D1") (pin "1") (pinfunction "A_1") (pintype "passive"))
      (node (ref "R27") (pin "2") (pinfunction "2_2") (pintype "passive"))
      (node (ref "R32") (pin "2") (pinfunction "2_2") (pintype "passive"))
      (node (ref "R33") (pin "2") (pinfunction "2_2") (pintype "passive"))
    )
    (net (code "33") (name "Net-(D1-K)") (class "Default")
      (node (ref "D1") (pin "2") (pinfunction "K_2") (pintype "passive"))
      (node (ref "D2") (pin "2") (pinfunction "K_2") (pintype "passive"))
    )
    (net (code "34") (name "Net-(D3-K)") (class "Default")
      (node (ref "D3") (pin "2") (pinfunction "K_2") (pintype "passive"))
      (node (ref "D4") (pin "1") (pinfunction "A_1") (pintype "passive"))
      (node (ref "R37") (pin "1") (pinfunction "1_1") (pintype "passive"))
      (node (ref "U10") (pin "5") (pinfunction "+IN2_5") (pintype "passive"))
    )
    (net (code "35") (name "Net-(D7-A)") (class "Default")
      (node (ref "C58") (pin "2") (pinfunction "2_2") (pintype "passive"))
      (node (ref "D7") (pin "1") (pinfunction "A_1") (pintype "passive"))
      (node (ref "R40") (pin "2") (pinfunction "2_2") (pintype "passive"))
      (node (ref "R45") (pin "2") (pinfunction "2_2") (pintype "passive"))
      (node (ref "R46") (pin "2") (pinfunction "2_2") (pintype "passive"))
    )
    (net (code "36") (name "Net-(D7-K)") (class "Default")
      (node (ref "D7") (pin "2") (pinfunction "K_2") (pintype "passive"))
      (node (ref "D8") (pin "2") (pinfunction "K_2") (pintype "passive"))
    )
    (net (code "37") (name "Net-(D10-A)") (class "Default")
      (node (ref "D10") (pin "1") (pinfunction "A_1") (pintype "passive"))
      (node (ref "D9") (pin "2") (pinfunction "K_2") (pintype "passive"))
      (node (ref "R50") (pin "1") (pinfunction "1_1") (pintype "passive"))
      (node (ref "U13") (pin "5") (pinfunction "+IN2_5") (pintype "passive"))
    )
    (net (code "38") (name "Net-(D13-A)") (class "Default")
      (node (ref "C66") (pin "2") (pinfunction "2_2") (pintype "passive"))
      (node (ref "D13") (pin "1") (pinfunction "A_1") (pintype "passive"))
      (node (ref "R53") (pin "2") (pinfunction "2_2") (pintype "passive"))
      (node (ref "R58") (pin "2") (pinfunction "2_2") (pintype "passive"))
      (node (ref "R59") (pin "2") (pinfunction "2_2") (pintype "passive"))
    )
    (net (code "39") (name "Net-(D13-K)") (class "Default")
      (node (ref "D13") (pin "2") (pinfunction "K_2") (pintype "passive"))
      (node (ref "D14") (pin "2") (pinfunction "K_2") (pintype "passive"))
    )
    (net (code "40") (name "Net-(D15-K)") (class "Default")
      (node (ref "D15") (pin "2") (pinfunction "K_2") (pintype "passive"))
      (node (ref "D16") (pin "1") (pinfunction "A_1") (pintype "passive"))
      (node (ref "R63") (pin "1") (pinfunction "1_1") (pintype "passive"))
      (node (ref "U16") (pin "5") (pinfunction "+IN2_5") (pintype "passive"))
    )
    (net (code "41") (name "Net-(D19-K)") (class "Default")
      (node (ref "CN15") (pin "1") (pinfunction "1_1") (pintype "passive"))
      (node (ref "D19") (pin "2") (pinfunction "K_2") (pintype "passive"))
      (node (ref "R68") (pin "2") (pinfunction "2_2") (pintype "passive"))
      (node (ref "R69") (pin "2") (pinfunction "2_2") (pintype "passive"))
      (node (ref "R70") (pin "2") (pinfunction "2_2") (pintype "passive"))
    )
    (net (code "42") (name "Net-(D20-K)") (class "Default")
      (node (ref "CN16") (pin "1") (pinfunction "1_1") (pintype "passive"))
      (node (ref "D20") (pin "2") (pinfunction "K_2") (pintype "passive"))
      (node (ref "R71") (pin "2") (pinfunction "2_2") (pintype "passive"))
      (node (ref "R72") (pin "2") (pinfunction "2_2") (pintype "passive"))
      (node (ref "R73") (pin "2") (pinfunction "2_2") (pintype "passive"))
    )
    (net (code "43") (name "Net-(R68-Pad1)") (class "Default")
      (node (ref "R68") (pin "1") (pinfunction "1_1") (pintype "passive"))
      (node (ref "R69") (pin "1") (pinfunction "1_1") (pintype "passive"))
      (node (ref "R70") (pin "1") (pinfunction "1_1") (pintype "passive"))
      (node (ref "TR1") (pin "2") (pinfunction "2_2") (pintype "passive"))
    )
    (net (code "44") (name "Net-(R71-Pad1)") (class "Default")
      (node (ref "R71") (pin "1") (pinfunction "1_1") (pintype "passive"))
      (node (ref "R72") (pin "1") (pinfunction "1_1") (pintype "passive"))
      (node (ref "R73") (pin "1") (pinfunction "1_1") (pintype "passive"))
      (node (ref "TR2") (pin "2") (pinfunction "2_2") (pintype "passive"))
    )
    (net (code "45") (name "Net-(U10A-+IN1)") (class "Default")
      (node (ref "R34") (pin "2") (pinfunction "2_2") (pintype "passive"))
      (node (ref "U10") (pin "3") (pinfunction "+IN1_3") (pintype "passive"))
    )
    (net (code "46") (name "Net-(U10A--IN1)") (class "Default")
      (node (ref "R28") (pin "1") (pinfunction "1_1") (pintype "passive"))
      (node (ref "U10") (pin "2") (pinfunction "-IN1_2") (pintype "passive"))
    )
    (net (code "47") (name "Net-(U10A-OUT1)") (class "Default")
      (node (ref "R28") (pin "2") (pinfunction "2_2") (pintype "passive"))
      (node (ref "R31") (pin "1") (pinfunction "1_1") (pintype "passive"))
      (node (ref "R37") (pin "2") (pinfunction "2_2") (pintype "passive"))
      (node (ref "U10") (pin "1") (pinfunction "OUT1_1") (pintype "passive"))
    )
    (net (code "48") (name "Net-(U10B--IN2)") (class "Default")
      (node (ref "R29") (pin "2") (pinfunction "2_2") (pintype "passive"))
      (node (ref "R30") (pin "1") (pinfunction "1_1") (pintype "passive"))
      (node (ref "U10") (pin "6") (pinfunction "-IN2_6") (pintype "passive"))
    )
    (net (code "49") (name "Net-(U10B-OUT1)") (class "Default")
      (node (ref "R30") (pin "2") (pinfunction "2_2") (pintype "passive"))
      (node (ref "R36") (pin "1") (pinfunction "1_1") (pintype "passive"))
      (node (ref "U10") (pin "7") (pinfunction "OUT1_7") (pintype "passive"))
    )
    (net (code "50") (name "Net-(U11-VIA)") (class "Default")
      (node (ref "U11") (pin "3") (pinfunction "VIA_3") (pintype "passive"))
      (node (ref "U12") (pin "7") (pinfunction "SO_7") (pintype "passive"))
    )
    (net (code "51") (name "Net-(U11-VOC)") (class "Default")
      (node (ref "U11") (pin "5") (pinfunction "VOC_5") (pintype "passive"))
      (node (ref "U12") (pin "6") (pinfunction "~{CS}_6") (pintype "passive"))
    )
    (net (code "52") (name "Net-(U11-VOD)") (class "Default")
      (node (ref "U11") (pin "6") (pinfunction "VOD_6") (pintype "passive"))
      (node (ref "U12") (pin "5") (pinfunction "SCK_5") (pintype "passive"))
    )
    (net (code "53") (name "Net-(U12-T+)") (class "Default")
      (node (ref "C57") (pin "1") (pinfunction "1_1") (pintype "passive"))
      (node (ref "CN9") (pin "1") (pinfunction "1_1") (pintype "passive"))
      (node (ref "U12") (pin "3") (pinfunction "T+_3") (pintype "passive"))
    )
    (net (code "54") (name "Net-(U12-T-)") (class "Default")
      (node (ref "C57") (pin "2") (pinfunction "2_2") (pintype "passive"))
      (node (ref "CN9") (pin "2") (pinfunction "2_2") (pintype "passive"))
      (node (ref "U12") (pin "2") (pinfunction "T-_2") (pintype "passive"))
    )
    (net (code "55") (name "Net-(U13A-+IN1)") (class "Default")
      (node (ref "R47") (pin "2") (pinfunction "2_2") (pintype "passive"))
      (node (ref "U13") (pin "3") (pinfunction "+IN1_3") (pintype "passive"))
    )
    (net (code "56") (name "Net-(U13A--IN1)") (class "Default")
      (node (ref "R41") (pin "1") (pinfunction "1_1") (pintype "passive"))
      (node (ref "U13") (pin "2") (pinfunction "-IN1_2") (pintype "passive"))
    )
    (net (code "57") (name "Net-(U13A-OUT1)") (class "Default")
      (node (ref "R41") (pin "2") (pinfunction "2_2") (pintype "passive"))
      (node (ref "R44") (pin "1") (pinfunction "1_1") (pintype "passive"))
      (node (ref "R50") (pin "2") (pinfunction "2_2") (pintype "passive"))
      (node (ref "U13") (pin "1") (pinfunction "OUT1_1") (pintype "passive"))
    )
    (net (code "58") (name "Net-(U13B--IN2)") (class "Default")
      (node (ref "R42") (pin "2") (pinfunction "2_2") (pintype "passive"))
      (node (ref "R43") (pin "1") (pinfunction "1_1") (pintype "passive"))
      (node (ref "U13") (pin "6") (pinfunction "-IN2_6") (pintype "passive"))
    )
    (net (code "59") (name "Net-(U13B-OUT1)") (class "Default")
      (node (ref "R43") (pin "2") (pinfunction "2_2") (pintype "passive"))
      (node (ref "R49") (pin "1") (pinfunction "1_1") (pintype "passive"))
      (node (ref "U13") (pin "7") (pinfunction "OUT1_7") (pintype "passive"))
    )
    (net (code "60") (name "Net-(U14-VIA)") (class "Default")
      (node (ref "U14") (pin "3") (pinfunction "VIA_3") (pintype "passive"))
      (node (ref "U15") (pin "7") (pinfunction "SO_7") (pintype "passive"))
    )
    (net (code "61") (name "Net-(U14-VOC)") (class "Default")
      (node (ref "U14") (pin "5") (pinfunction "VOC_5") (pintype "passive"))
      (node (ref "U15") (pin "6") (pinfunction "~{CS}_6") (pintype "passive"))
    )
    (net (code "62") (name "Net-(U14-VOD)") (class "Default")
      (node (ref "U14") (pin "6") (pinfunction "VOD_6") (pintype "passive"))
      (node (ref "U15") (pin "5") (pinfunction "SCK_5") (pintype "passive"))
    )
    (net (code "63") (name "Net-(U15-T+)") (class "Default")
      (node (ref "C65") (pin "1") (pinfunction "1_1") (pintype "passive"))
      (node (ref "CN11") (pin "1") (pinfunction "1_1") (pintype "passive"))
      (node (ref "U15") (pin "3") (pinfunction "T+_3") (pintype "passive"))
    )
    (net (code "64") (name "Net-(U15-T-)") (class "Default")
      (node (ref "C65") (pin "2") (pinfunction "2_2") (pintype "passive"))
      (node (ref "CN11") (pin "2") (pinfunction "2_2") (pintype "passive"))
      (node (ref "U15") (pin "2") (pinfunction "T-_2") (pintype "passive"))
    )
    (net (code "65") (name "Net-(U16A-+IN1)") (class "Default")
      (node (ref "R60") (pin "2") (pinfunction "2_2") (pintype "passive"))
      (node (ref "U16") (pin "3") (pinfunction "+IN1_3") (pintype "passive"))
    )
    (net (code "66") (name "Net-(U16A--IN1)") (class "Default")
      (node (ref "R54") (pin "1") (pinfunction "1_1") (pintype "passive"))
      (node (ref "U16") (pin "2") (pinfunction "-IN1_2") (pintype "passive"))
    )
    (net (code "67") (name "Net-(U16A-OUT1)") (class "Default")
      (node (ref "R54") (pin "2") (pinfunction "2_2") (pintype "passive"))
      (node (ref "R57") (pin "1") (pinfunction "1_1") (pintype "passive"))
      (node (ref "R63") (pin "2") (pinfunction "2_2") (pintype "passive"))
      (node (ref "U16") (pin "1") (pinfunction "OUT1_1") (pintype "passive"))
    )
    (net (code "68") (name "Net-(U16B--IN2)") (class "Default")
      (node (ref "R55") (pin "2") (pinfunction "2_2") (pintype "passive"))
      (node (ref "R56") (pin "1") (pinfunction "1_1") (pintype "passive"))
      (node (ref "U16") (pin "6") (pinfunction "-IN2_6") (pintype "passive"))
    )
    (net (code "69") (name "Net-(U16B-OUT1)") (class "Default")
      (node (ref "R56") (pin "2") (pinfunction "2_2") (pintype "passive"))
      (node (ref "R62") (pin "1") (pinfunction "1_1") (pintype "passive"))
      (node (ref "U16") (pin "7") (pinfunction "OUT1_7") (pintype "passive"))
    )
    (net (code "70") (name "unconnected-(U11-NIC-Pad8)") (class "Default")
      (node (ref "U11") (pin "8") (pinfunction "NIC_8") (pintype "passive+no_connect"))
    )
    (net (code "71") (name "unconnected-(U11-NIC-Pad9)") (class "Default")
      (node (ref "U11") (pin "9") (pinfunction "NIC_9") (pintype "passive+no_connect"))
    )
    (net (code "72") (name "unconnected-(U11-NIC-Pad12)") (class "Default")
      (node (ref "U11") (pin "12") (pinfunction "NIC_12") (pintype "passive+no_connect"))
    )
    (net (code "73") (name "unconnected-(U11-NIC-Pad13)") (class "Default")
      (node (ref "U11") (pin "13") (pinfunction "NIC_13") (pintype "passive+no_connect"))
    )
    (net (code "74") (name "unconnected-(U11-VOB-Pad17)") (class "Default")
      (node (ref "U11") (pin "17") (pinfunction "VOB_17") (pintype "passive+no_connect"))
    )
    (net (code "75") (name "unconnected-(U12-DNC-Pad8)") (class "Default")
      (node (ref "U12") (pin "8") (pinfunction "DNC_8") (pintype "passive+no_connect"))
    )
    (net (code "76") (name "unconnected-(U14-NIC-Pad8)") (class "Default")
      (node (ref "U14") (pin "8") (pinfunction "NIC_8") (pintype "passive+no_connect"))
    )
    (net (code "77") (name "unconnected-(U14-NIC-Pad9)") (class "Default")
      (node (ref "U14") (pin "9") (pinfunction "NIC_9") (pintype "passive+no_connect"))
    )
    (net (code "78") (name "unconnected-(U14-NIC-Pad12)") (class "Default")
      (node (ref "U14") (pin "12") (pinfunction "NIC_12") (pintype "passive+no_connect"))
    )
    (net (code "79") (name "unconnected-(U14-NIC-Pad13)") (class "Default")
      (node (ref "U14") (pin "13") (pinfunction "NIC_13") (pintype "passive+no_connect"))
    )
    (net (code "80") (name "unconnected-(U14-VOB-Pad17)") (class "Default")
      (node (ref "U14") (pin "17") (pinfunction "VOB_17") (pintype "passive+no_connect"))
    )
    (net (code "81") (name "unconnected-(U15-DNC-Pad8)") (class "Default")
      (node (ref "U15") (pin "8") (pinfunction "DNC_8") (pintype "passive+no_connect"))
    )
  )
)
